# PRTF02.net
KiCad netlist of a schematic drawn in EAGLE
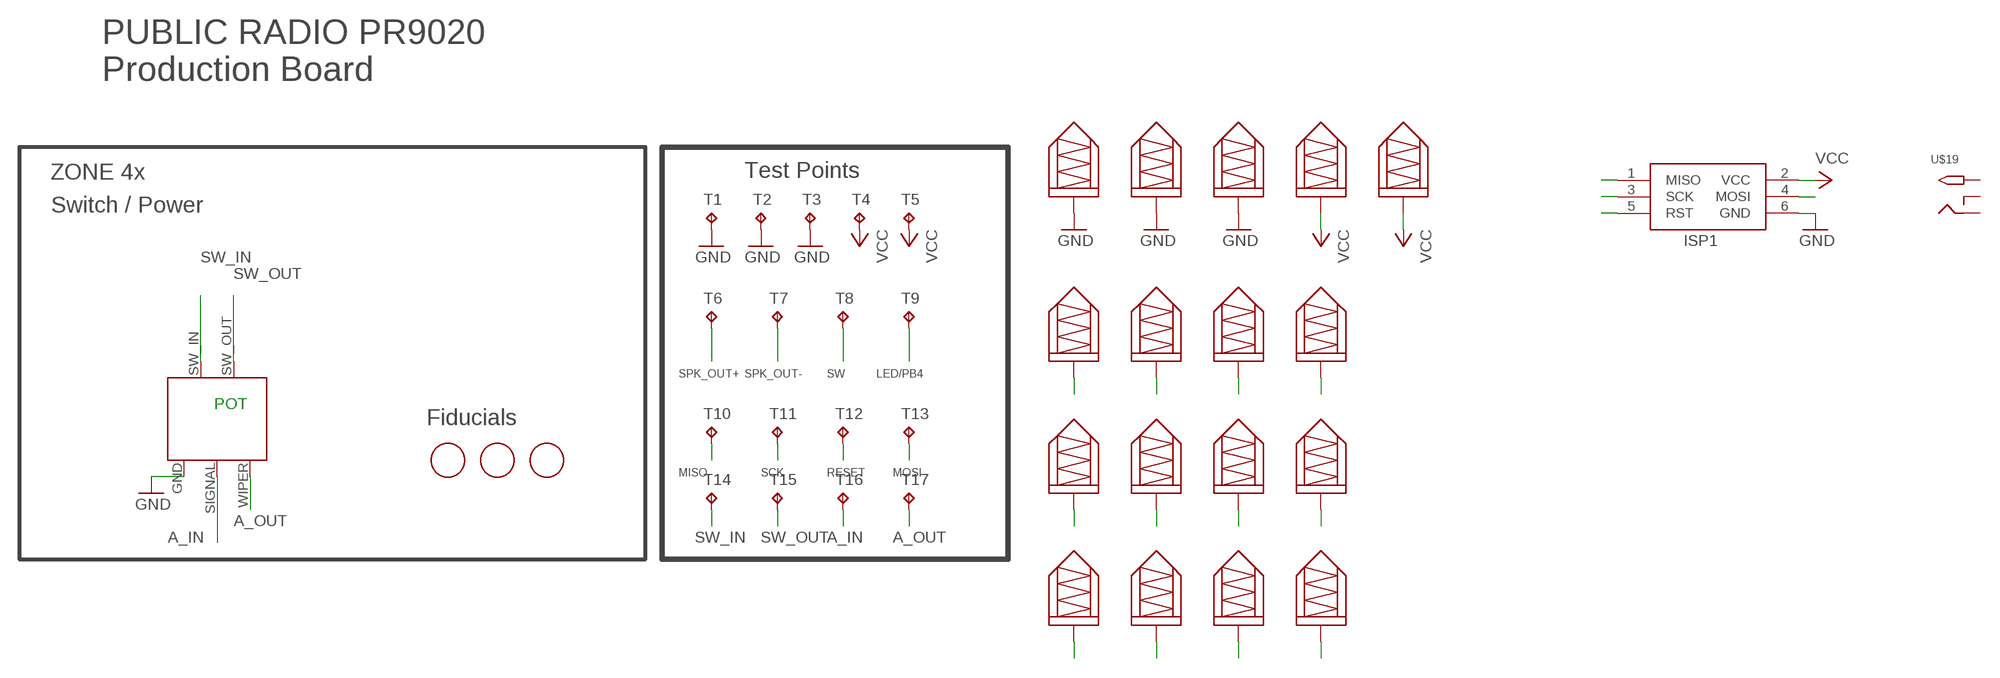
[diagram p0: schematic, sheet 1]

(export (version "E")
  (design (tool "Eeschema 10.0.6"))
  (components
    (comp (ref "ISP1")
      (value "AVRISP-6")
      (footprint "eagle-import:AVRISP")
      (libsource (lib "eagle-import") (part "AVRISP-6"))
    )
    (comp (ref "MARK1")
      (value "FIDUCIAL")
      (footprint "eagle-import:FIDUCIAL_1MM")
      (libsource (lib "eagle-import") (part "FIDUCIAL"))
    )
    (comp (ref "MARK2")
      (value "FIDUCIAL")
      (footprint "eagle-import:FIDUCIAL_1MM")
      (libsource (lib "eagle-import") (part "FIDUCIAL"))
    )
    (comp (ref "MARK3")
      (value "FIDUCIAL")
      (footprint "eagle-import:FIDUCIAL_1MM")
      (libsource (lib "eagle-import") (part "FIDUCIAL"))
    )
    (comp (ref "R1")
      (value "RV170SF_TAIWANA_POT_SW")
      (footprint "eagle-import:RV170SF_SW_POT")
      (fields (field (name "MFG_PN") "RV170SF-43-20F-A10K - supplied by CL Labs"))
      (libsource (lib "eagle-import") (part "RV170SF_TAIWANA_POT_SW"))
    )
    (comp (ref "T1")
      (value "TPTP20R")
      (footprint "eagle-import:TP20R")
      (libsource (lib "eagle-import") (part "TPTP20R"))
    )
    (comp (ref "T2")
      (value "TPTP20R")
      (footprint "eagle-import:TP20R")
      (libsource (lib "eagle-import") (part "TPTP20R"))
    )
    (comp (ref "T3")
      (value "TPTP20R")
      (footprint "eagle-import:TP20R")
      (libsource (lib "eagle-import") (part "TPTP20R"))
    )
    (comp (ref "T4")
      (value "TPTP20R")
      (footprint "eagle-import:TP20R")
      (libsource (lib "eagle-import") (part "TPTP20R"))
    )
    (comp (ref "T5")
      (value "TPTP20R")
      (footprint "eagle-import:TP20R")
      (libsource (lib "eagle-import") (part "TPTP20R"))
    )
    (comp (ref "T6")
      (value "TPTP20R")
      (footprint "eagle-import:TP20R")
      (libsource (lib "eagle-import") (part "TPTP20R"))
    )
    (comp (ref "T7")
      (value "TPTP20R")
      (footprint "eagle-import:TP20R")
      (libsource (lib "eagle-import") (part "TPTP20R"))
    )
    (comp (ref "T8")
      (value "TPTP20R")
      (footprint "eagle-import:TP20R")
      (libsource (lib "eagle-import") (part "TPTP20R"))
    )
    (comp (ref "T9")
      (value "TPTP20R")
      (footprint "eagle-import:TP20R")
      (libsource (lib "eagle-import") (part "TPTP20R"))
    )
    (comp (ref "T10")
      (value "TPTP20R")
      (footprint "eagle-import:TP20R")
      (libsource (lib "eagle-import") (part "TPTP20R"))
    )
    (comp (ref "T11")
      (value "TPTP20R")
      (footprint "eagle-import:TP20R")
      (libsource (lib "eagle-import") (part "TPTP20R"))
    )
    (comp (ref "T12")
      (value "TPTP20R")
      (footprint "eagle-import:TP20R")
      (libsource (lib "eagle-import") (part "TPTP20R"))
    )
    (comp (ref "T13")
      (value "TPTP20R")
      (footprint "eagle-import:TP20R")
      (libsource (lib "eagle-import") (part "TPTP20R"))
    )
    (comp (ref "T14")
      (value "TPTP20R")
      (footprint "eagle-import:TP20R")
      (libsource (lib "eagle-import") (part "TPTP20R"))
    )
    (comp (ref "T15")
      (value "TPTP20R")
      (footprint "eagle-import:TP20R")
      (libsource (lib "eagle-import") (part "TPTP20R"))
    )
    (comp (ref "T16")
      (value "TPTP20R")
      (footprint "eagle-import:TP20R")
      (libsource (lib "eagle-import") (part "TPTP20R"))
    )
    (comp (ref "T17")
      (value "TPTP20R")
      (footprint "eagle-import:TP20R")
      (libsource (lib "eagle-import") (part "TPTP20R"))
    )
    (comp (ref "U$2")
      (value "0908MILL_MAX_SPRINGPIN")
      (footprint "eagle-import:0908MILL_MAX_SPRINGPIN")
      (libsource (lib "eagle-import") (part "0908MILL_MAX_SPRINGPIN"))
    )
    (comp (ref "U$3")
      (value "0908MILL_MAX_SPRINGPIN")
      (footprint "eagle-import:0908MILL_MAX_SPRINGPIN")
      (libsource (lib "eagle-import") (part "0908MILL_MAX_SPRINGPIN"))
    )
    (comp (ref "U$4")
      (value "0908MILL_MAX_SPRINGPIN")
      (footprint "eagle-import:0908MILL_MAX_SPRINGPIN")
      (libsource (lib "eagle-import") (part "0908MILL_MAX_SPRINGPIN"))
    )
    (comp (ref "U$5")
      (value "0908MILL_MAX_SPRINGPIN")
      (footprint "eagle-import:0908MILL_MAX_SPRINGPIN")
      (libsource (lib "eagle-import") (part "0908MILL_MAX_SPRINGPIN"))
    )
    (comp (ref "U$6")
      (value "0908MILL_MAX_SPRINGPIN")
      (footprint "eagle-import:0908MILL_MAX_SPRINGPIN")
      (libsource (lib "eagle-import") (part "0908MILL_MAX_SPRINGPIN"))
    )
    (comp (ref "U$7")
      (value "0908MILL_MAX_SPRINGPIN")
      (footprint "eagle-import:0908MILL_MAX_SPRINGPIN")
      (libsource (lib "eagle-import") (part "0908MILL_MAX_SPRINGPIN"))
    )
    (comp (ref "U$8")
      (value "0908MILL_MAX_SPRINGPIN")
      (footprint "eagle-import:0908MILL_MAX_SPRINGPIN")
      (libsource (lib "eagle-import") (part "0908MILL_MAX_SPRINGPIN"))
    )
    (comp (ref "U$9")
      (value "0908MILL_MAX_SPRINGPIN")
      (footprint "eagle-import:0908MILL_MAX_SPRINGPIN")
      (libsource (lib "eagle-import") (part "0908MILL_MAX_SPRINGPIN"))
    )
    (comp (ref "U$10")
      (value "0908MILL_MAX_SPRINGPIN")
      (footprint "eagle-import:0908MILL_MAX_SPRINGPIN")
      (libsource (lib "eagle-import") (part "0908MILL_MAX_SPRINGPIN"))
    )
    (comp (ref "U$11")
      (value "0908MILL_MAX_SPRINGPIN")
      (footprint "eagle-import:0908MILL_MAX_SPRINGPIN")
      (libsource (lib "eagle-import") (part "0908MILL_MAX_SPRINGPIN"))
    )
    (comp (ref "U$12")
      (value "0908MILL_MAX_SPRINGPIN")
      (footprint "eagle-import:0908MILL_MAX_SPRINGPIN")
      (libsource (lib "eagle-import") (part "0908MILL_MAX_SPRINGPIN"))
    )
    (comp (ref "U$13")
      (value "0908MILL_MAX_SPRINGPIN")
      (footprint "eagle-import:0908MILL_MAX_SPRINGPIN")
      (libsource (lib "eagle-import") (part "0908MILL_MAX_SPRINGPIN"))
    )
    (comp (ref "U$14")
      (value "0908MILL_MAX_SPRINGPIN")
      (footprint "eagle-import:0908MILL_MAX_SPRINGPIN")
      (libsource (lib "eagle-import") (part "0908MILL_MAX_SPRINGPIN"))
    )
    (comp (ref "U$15")
      (value "0908MILL_MAX_SPRINGPIN")
      (footprint "eagle-import:0908MILL_MAX_SPRINGPIN")
      (libsource (lib "eagle-import") (part "0908MILL_MAX_SPRINGPIN"))
    )
    (comp (ref "U$16")
      (value "0908MILL_MAX_SPRINGPIN")
      (footprint "eagle-import:0908MILL_MAX_SPRINGPIN")
      (libsource (lib "eagle-import") (part "0908MILL_MAX_SPRINGPIN"))
    )
    (comp (ref "U$17")
      (value "0908MILL_MAX_SPRINGPIN")
      (footprint "eagle-import:0908MILL_MAX_SPRINGPIN")
      (libsource (lib "eagle-import") (part "0908MILL_MAX_SPRINGPIN"))
    )
    (comp (ref "U$18")
      (value "0908MILL_MAX_SPRINGPIN")
      (footprint "eagle-import:0908MILL_MAX_SPRINGPIN")
      (libsource (lib "eagle-import") (part "0908MILL_MAX_SPRINGPIN"))
    )
    (comp (ref "U$19")
      (value "2.1MMJACKTHM")
      (footprint "eagle-import:PJ-102A")
      (libsource (lib "eagle-import") (part "2.1MMJACKTHM"))
    )
  )
  (nets
    (net (code "1") (name "/A_IN") (class "Default")
      (node (ref "R1") (pin "SIGNAL") (pinfunction "SIGNAL_SIGNAL") (pintype "bidirectional"))
      (node (ref "T16") (pin "TP") (pinfunction "TP_TP") (pintype "input"))
      (node (ref "U$17") (pin "P$1") (pinfunction "P$1_P$1") (pintype "bidirectional"))
    )
    (net (code "2") (name "/A_OUT") (class "Default")
      (node (ref "R1") (pin "WIPER") (pinfunction "WIPER_WIPER") (pintype "bidirectional"))
      (node (ref "T17") (pin "TP") (pinfunction "TP_TP") (pintype "input"))
      (node (ref "U$18") (pin "P$1") (pinfunction "P$1_P$1") (pintype "bidirectional"))
    )
    (net (code "3") (name "/LED{slash}PB4") (class "Default")
      (node (ref "T9") (pin "TP") (pinfunction "TP_TP") (pintype "input"))
      (node (ref "U$10") (pin "P$1") (pinfunction "P$1_P$1") (pintype "bidirectional"))
    )
    (net (code "4") (name "/MISO") (class "Default")
      (node (ref "ISP1") (pin "1") (pinfunction "MISO_1") (pintype "input"))
      (node (ref "U$11") (pin "P$1") (pinfunction "P$1_P$1") (pintype "bidirectional"))
    )
    (net (code "5") (name "/MOSI") (class "Default")
      (node (ref "ISP1") (pin "4") (pinfunction "MOSI_4") (pintype "output"))
      (node (ref "U$14") (pin "P$1") (pinfunction "P$1_P$1") (pintype "bidirectional"))
    )
    (net (code "6") (name "/RESET") (class "Default")
      (node (ref "T12") (pin "TP") (pinfunction "TP_TP") (pintype "input"))
      (node (ref "U$13") (pin "P$1") (pinfunction "P$1_P$1") (pintype "bidirectional"))
    )
    (net (code "7") (name "/SCK") (class "Default")
      (node (ref "ISP1") (pin "3") (pinfunction "SCK_3") (pintype "output"))
      (node (ref "U$12") (pin "P$1") (pinfunction "P$1_P$1") (pintype "bidirectional"))
    )
    (net (code "8") (name "/SPK_OUT+") (class "Default")
      (node (ref "T6") (pin "TP") (pinfunction "TP_TP") (pintype "input"))
      (node (ref "U$7") (pin "P$1") (pinfunction "P$1_P$1") (pintype "bidirectional"))
    )
    (net (code "9") (name "/SPK_OUT-") (class "Default")
      (node (ref "T7") (pin "TP") (pinfunction "TP_TP") (pintype "input"))
      (node (ref "U$8") (pin "P$1") (pinfunction "P$1_P$1") (pintype "bidirectional"))
    )
    (net (code "10") (name "/SW") (class "Default")
      (node (ref "T8") (pin "TP") (pinfunction "TP_TP") (pintype "input"))
      (node (ref "U$9") (pin "P$1") (pinfunction "P$1_P$1") (pintype "bidirectional"))
    )
    (net (code "11") (name "/SW_IN") (class "Default")
      (node (ref "R1") (pin "SW_IN") (pinfunction "SW_IN_SW_IN") (pintype "bidirectional"))
      (node (ref "T14") (pin "TP") (pinfunction "TP_TP") (pintype "input"))
      (node (ref "U$15") (pin "P$1") (pinfunction "P$1_P$1") (pintype "bidirectional"))
    )
    (net (code "12") (name "/SW_OUT") (class "Default")
      (node (ref "R1") (pin "SW_OUT") (pinfunction "SW_OUT_SW_OUT") (pintype "bidirectional"))
      (node (ref "T15") (pin "TP") (pinfunction "TP_TP") (pintype "input"))
      (node (ref "U$16") (pin "P$1") (pinfunction "P$1_P$1") (pintype "bidirectional"))
    )
    (net (code "13") (name "GND") (class "Default")
      (node (ref "ISP1") (pin "6") (pinfunction "GND_6") (pintype "power_in"))
      (node (ref "R1") (pin "GND") (pinfunction "GND_GND") (pintype "bidirectional"))
      (node (ref "T1") (pin "TP") (pinfunction "TP_TP") (pintype "input"))
      (node (ref "T2") (pin "TP") (pinfunction "TP_TP") (pintype "input"))
      (node (ref "T3") (pin "TP") (pinfunction "TP_TP") (pintype "input"))
      (node (ref "U$2") (pin "P$1") (pinfunction "P$1_P$1") (pintype "bidirectional"))
      (node (ref "U$3") (pin "P$1") (pinfunction "P$1_P$1") (pintype "bidirectional"))
      (node (ref "U$4") (pin "P$1") (pinfunction "P$1_P$1") (pintype "bidirectional"))
    )
    (net (code "14") (name "VCC") (class "Default")
      (node (ref "ISP1") (pin "2") (pinfunction "VCC_2") (pintype "power_in"))
      (node (ref "T4") (pin "TP") (pinfunction "TP_TP") (pintype "input"))
      (node (ref "T5") (pin "TP") (pinfunction "TP_TP") (pintype "input"))
      (node (ref "U$5") (pin "P$1") (pinfunction "P$1_P$1") (pintype "bidirectional"))
      (node (ref "U$6") (pin "P$1") (pinfunction "P$1_P$1") (pintype "bidirectional"))
    )
    (net (code "15") (name "unconnected-(ISP1-RST-Pad5)") (class "Default")
      (node (ref "ISP1") (pin "5") (pinfunction "RST_5") (pintype "output"))
    )
    (net (code "16") (name "unconnected-(T10-PadTP)") (class "Default")
      (node (ref "T10") (pin "TP") (pinfunction "TP_TP") (pintype "input"))
    )
    (net (code "17") (name "unconnected-(T11-PadTP)") (class "Default")
      (node (ref "T11") (pin "TP") (pinfunction "TP_TP") (pintype "input"))
    )
    (net (code "18") (name "unconnected-(T13-PadTP)") (class "Default")
      (node (ref "T13") (pin "TP") (pinfunction "TP_TP") (pintype "input"))
    )
    (net (code "19") (name "unconnected-(U$19-PadRING)") (class "Default")
      (node (ref "U$19") (pin "RING") (pinfunction "RING_RING") (pintype "bidirectional"))
    )
    (net (code "20") (name "unconnected-(U$19-PadRING_SW)") (class "Default")
      (node (ref "U$19") (pin "RING_SW") (pinfunction "RING_SW_RING_SW") (pintype "bidirectional"))
    )
    (net (code "21") (name "unconnected-(U$19-PadTIP)") (class "Default")
      (node (ref "U$19") (pin "TIP") (pinfunction "TIP_TIP") (pintype "bidirectional"))
    )
  )
)
